# esp8285-miniboard-v1_0.net
KiCad netlist of a schematic drawn in EAGLE
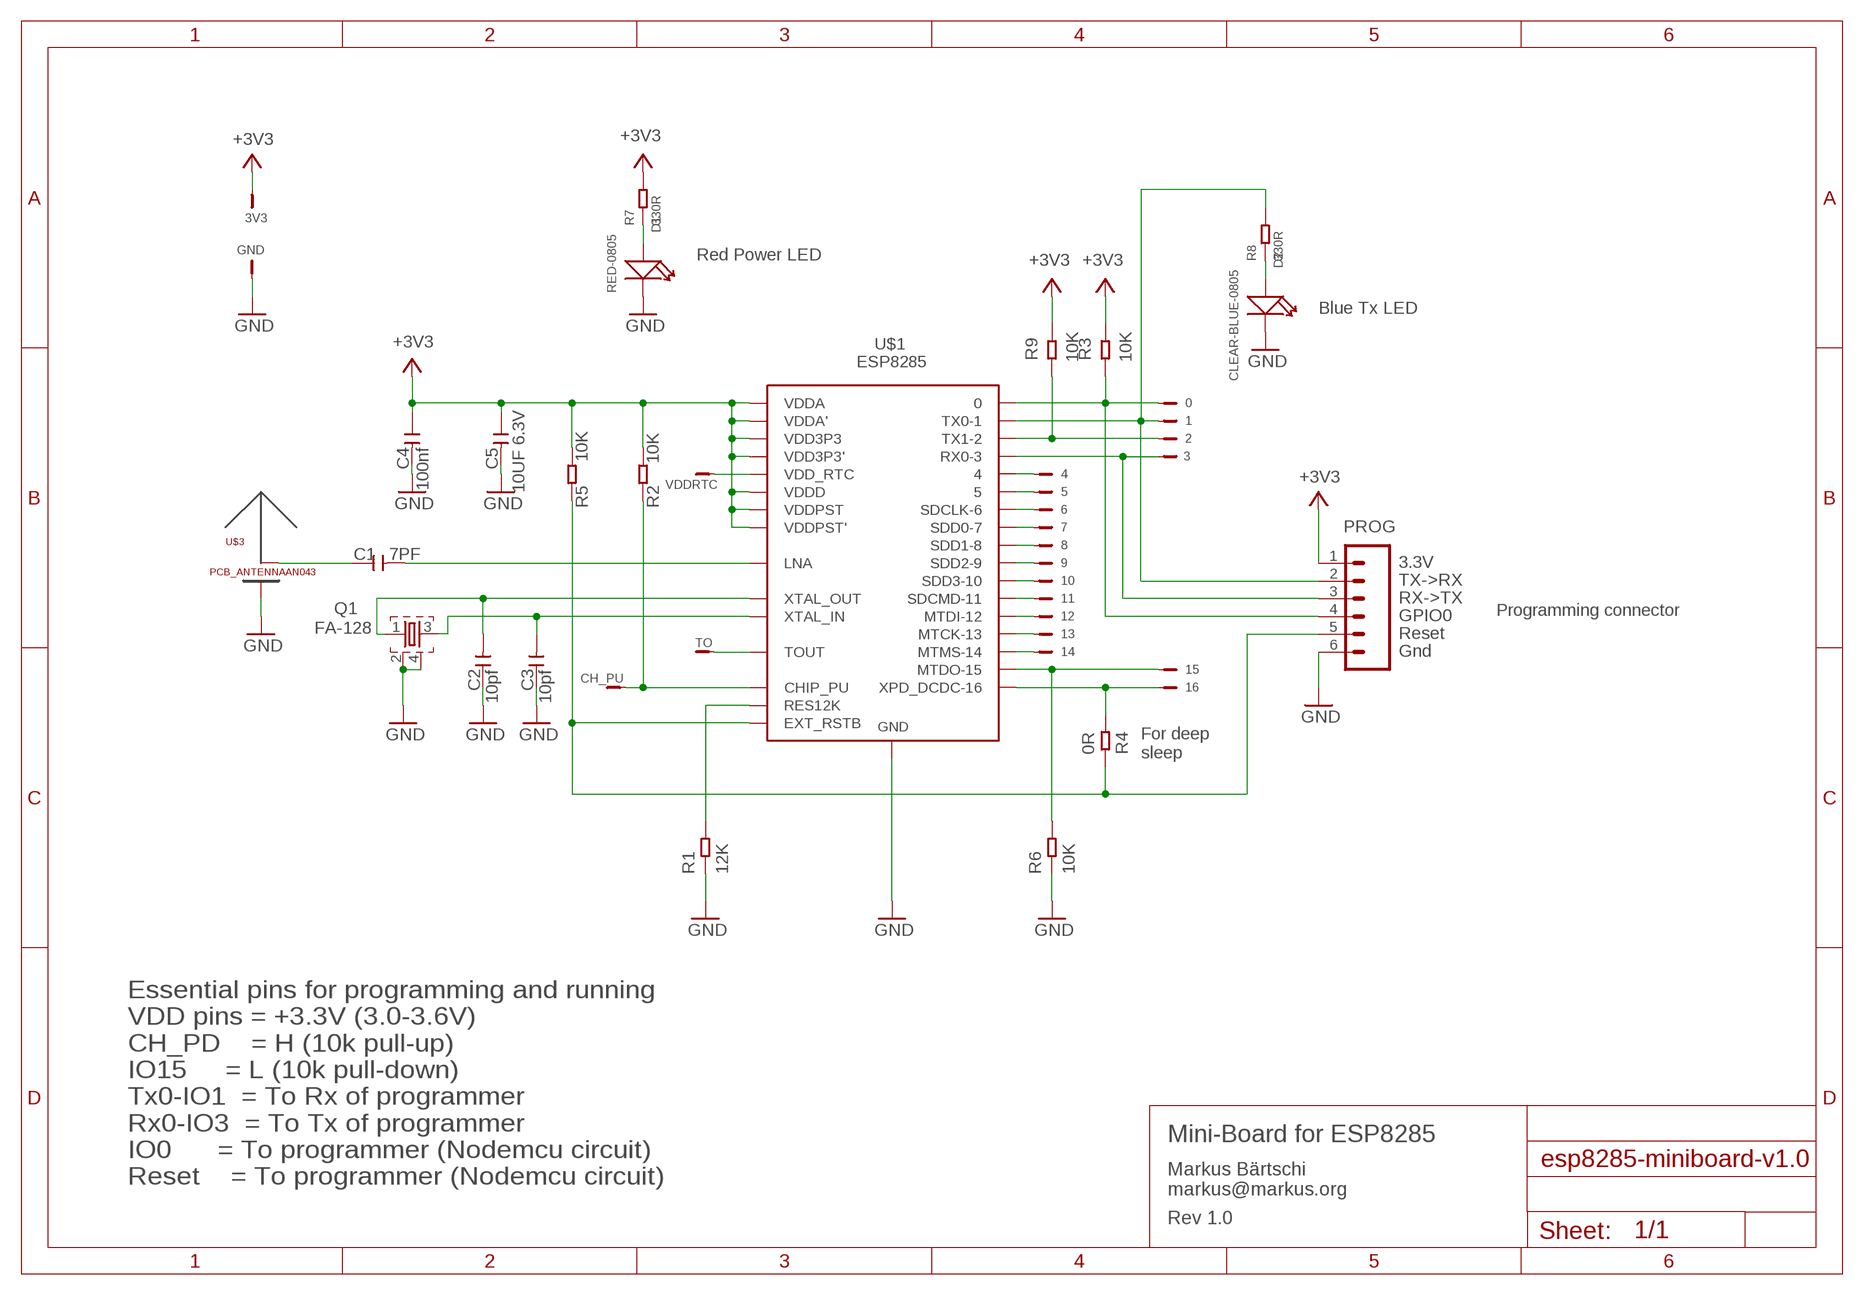
[diagram p0: schematic, sheet 1]

(export (version "E")
  (design (tool "Eeschema 10.0.6"))
  (components
    (comp (ref "0")
      (value "TESTPIN-1X1-SM")
      (footprint "eagle-import:TESTPIN-HDR1X01")
      (libsource (lib "eagle-import") (part "TESTPIN-1X1-SM"))
    )
    (comp (ref "1")
      (value "TESTPIN-1X1-SM")
      (footprint "eagle-import:TESTPIN-HDR1X01")
      (libsource (lib "eagle-import") (part "TESTPIN-1X1-SM"))
    )
    (comp (ref "2")
      (value "TESTPIN-1X1-SM")
      (footprint "eagle-import:TESTPIN-HDR1X01")
      (libsource (lib "eagle-import") (part "TESTPIN-1X1-SM"))
    )
    (comp (ref "3")
      (value "TESTPIN-1X1-SM")
      (footprint "eagle-import:TESTPIN-HDR1X01")
      (libsource (lib "eagle-import") (part "TESTPIN-1X1-SM"))
    )
    (comp (ref "3V3")
      (value "TESTPIN-1X1-SM")
      (footprint "eagle-import:TESTPIN-HDR1X01")
      (libsource (lib "eagle-import") (part "TESTPIN-1X1-SM"))
    )
    (comp (ref "4")
      (value "TESTPIN-1X1-SM")
      (footprint "eagle-import:TESTPIN-HDR1X01")
      (libsource (lib "eagle-import") (part "TESTPIN-1X1-SM"))
    )
    (comp (ref "5")
      (value "TESTPIN-1X1-SM")
      (footprint "eagle-import:TESTPIN-HDR1X01")
      (libsource (lib "eagle-import") (part "TESTPIN-1X1-SM"))
    )
    (comp (ref "6")
      (value "TESTPIN-1X1-SM")
      (footprint "eagle-import:TESTPIN-HDR1X01")
      (libsource (lib "eagle-import") (part "TESTPIN-1X1-SM"))
    )
    (comp (ref "7")
      (value "TESTPIN-1X1-SM")
      (footprint "eagle-import:TESTPIN-HDR1X01")
      (libsource (lib "eagle-import") (part "TESTPIN-1X1-SM"))
    )
    (comp (ref "8")
      (value "TESTPIN-1X1-SM")
      (footprint "eagle-import:TESTPIN-HDR1X01")
      (libsource (lib "eagle-import") (part "TESTPIN-1X1-SM"))
    )
    (comp (ref "9")
      (value "TESTPIN-1X1-SM")
      (footprint "eagle-import:TESTPIN-HDR1X01")
      (libsource (lib "eagle-import") (part "TESTPIN-1X1-SM"))
    )
    (comp (ref "10")
      (value "TESTPIN-1X1-SM")
      (footprint "eagle-import:TESTPIN-HDR1X01")
      (libsource (lib "eagle-import") (part "TESTPIN-1X1-SM"))
    )
    (comp (ref "11")
      (value "TESTPIN-1X1-SM")
      (footprint "eagle-import:TESTPIN-HDR1X01")
      (libsource (lib "eagle-import") (part "TESTPIN-1X1-SM"))
    )
    (comp (ref "12")
      (value "TESTPIN-1X1-SM")
      (footprint "eagle-import:TESTPIN-HDR1X01")
      (libsource (lib "eagle-import") (part "TESTPIN-1X1-SM"))
    )
    (comp (ref "13")
      (value "TESTPIN-1X1-SM")
      (footprint "eagle-import:TESTPIN-HDR1X01")
      (libsource (lib "eagle-import") (part "TESTPIN-1X1-SM"))
    )
    (comp (ref "14")
      (value "TESTPIN-1X1-SM")
      (footprint "eagle-import:TESTPIN-HDR1X01")
      (libsource (lib "eagle-import") (part "TESTPIN-1X1-SM"))
    )
    (comp (ref "15")
      (value "TESTPIN-1X1-SM")
      (footprint "eagle-import:TESTPIN-HDR1X01")
      (libsource (lib "eagle-import") (part "TESTPIN-1X1-SM"))
    )
    (comp (ref "16")
      (value "TESTPIN-1X1-SM")
      (footprint "eagle-import:TESTPIN-HDR1X01")
      (libsource (lib "eagle-import") (part "TESTPIN-1X1-SM"))
    )
    (comp (ref "C1")
      (value "7PF")
      (footprint "eagle-import:C0603")
      (libsource (lib "eagle-import") (part "CERAMIC-7PF-50V-0.5PF-NPO(0603)"))
    )
    (comp (ref "C2")
      (value "10pf")
      (footprint "eagle-import:C0603")
      (libsource (lib "eagle-import") (part "CERAMIC-10PF-50V-5%-NPO(0603)"))
    )
    (comp (ref "C3")
      (value "10pf")
      (footprint "eagle-import:C0603")
      (libsource (lib "eagle-import") (part "CERAMIC-10PF-50V-5%-NPO(0603)"))
    )
    (comp (ref "C4")
      (value "100nf")
      (footprint "eagle-import:C0603")
      (fields (field (name "MPN") "CC0603KRX7R9BB104"))
      (libsource (lib "eagle-import") (part "CERAMIC-100NF-50V-10%-X7R(0603)"))
    )
    (comp (ref "C5")
      (value "10UF 6.3V")
      (footprint "eagle-import:C0603")
      (fields (field (name "MPN") "CC0603MRX5R5BB106"))
      (libsource (lib "eagle-import") (part "CERAMIC-10UF-6.3V-20%-X5R(0603)"))
    )
    (comp (ref "CH_PU")
      (value "TESTPIN-1X1-SM")
      (footprint "eagle-import:TESTPIN-HDR1X01")
      (libsource (lib "eagle-import") (part "TESTPIN-1X1-SM"))
    )
    (comp (ref "D1")
      (value "RED-0805")
      (footprint "eagle-import:LED-0805")
      (fields (field (name "MPN") "17-215SURC/S530-A2/TR8"))
      (libsource (lib "eagle-import") (part "SMD-LED-CLEAR-RED(0805)"))
    )
    (comp (ref "D2")
      (value "CLEAR-BLUE-0805")
      (footprint "eagle-import:LED-0805")
      (fields (field (name "MPN") "EL-17-215/BHC-AN1P2/3T"))
      (libsource (lib "eagle-import") (part "SMD-LED-CLEAR-BLUE(0805)"))
    )
    (comp (ref "GND")
      (value "TESTPIN-1X1-SM")
      (footprint "eagle-import:TESTPIN-HDR1X01")
      (libsource (lib "eagle-import") (part "TESTPIN-1X1-SM"))
    )
    (comp (ref "PROG")
      (value "M06SIP")
      (footprint "eagle-import:1X06")
      (libsource (lib "eagle-import") (part "M06SIP"))
    )
    (comp (ref "Q1")
      (value "FA-128")
      (footprint "eagle-import:FA-128")
      (libsource (lib "eagle-import") (part "FA-128"))
    )
    (comp (ref "R1")
      (value "12K")
      (footprint "eagle-import:R0603")
      (fields (field (name "MPN") "RC0603FR-0712KL"))
      (libsource (lib "eagle-import") (part "SMD-RES-12K-1%-1/10W(0603)"))
    )
    (comp (ref "R2")
      (value "10K")
      (footprint "eagle-import:R0603")
      (fields (field (name "MPN") "RC0603FR-0710KL"))
      (libsource (lib "eagle-import") (part "SMD-RES-10K-1%-1/10W(0603)"))
    )
    (comp (ref "R3")
      (value "10K")
      (footprint "eagle-import:R0603")
      (fields (field (name "MPN") "RC0603FR-0710KL"))
      (libsource (lib "eagle-import") (part "SMD-RES-10K-1%-1/10W(0603)"))
    )
    (comp (ref "R4")
      (value "0R")
      (footprint "eagle-import:R0603")
      (fields (field (name "MPN") "RC0603JR-070RL"))
      (libsource (lib "eagle-import") (part "SMD-RES-0R-5%-1/10W(0603)"))
    )
    (comp (ref "R5")
      (value "10K")
      (footprint "eagle-import:R0603")
      (fields (field (name "MPN") "RC0603FR-0710KL"))
      (libsource (lib "eagle-import") (part "SMD-RES-10K-1%-1/10W(0603)"))
    )
    (comp (ref "R6")
      (value "10K")
      (footprint "eagle-import:R0603")
      (fields (field (name "MPN") "RC0603FR-0710KL"))
      (libsource (lib "eagle-import") (part "SMD-RES-10K-1%-1/10W(0603)"))
    )
    (comp (ref "R7")
      (value "330R")
      (footprint "eagle-import:R0603")
      (fields (field (name "MPN") "RC0603FR-07330RL"))
      (libsource (lib "eagle-import") (part "SMD-RES-330R-1%-1/10W(0603)"))
    )
    (comp (ref "R8")
      (value "330R")
      (footprint "eagle-import:R0603")
      (fields (field (name "MPN") "RC0603FR-07330RL"))
      (libsource (lib "eagle-import") (part "SMD-RES-330R-1%-1/10W(0603)"))
    )
    (comp (ref "R9")
      (value "10K")
      (footprint "eagle-import:R0603")
      (fields (field (name "MPN") "RC0603FR-0710KL"))
      (libsource (lib "eagle-import") (part "SMD-RES-10K-1%-1/10W(0603)"))
    )
    (comp (ref "TO")
      (value "TESTPIN-1X1-SM")
      (footprint "eagle-import:TESTPIN-HDR1X01")
      (libsource (lib "eagle-import") (part "TESTPIN-1X1-SM"))
    )
    (comp (ref "U$1")
      (value "ESP8285")
      (footprint "eagle-import:QFN-32")
      (libsource (lib "eagle-import") (part "ESP8285"))
    )
    (comp (ref "U$3")
      (value "PCB_ANTENNAAN043")
      (footprint "eagle-import:PCB_ANTENNA_TI-AN043")
      (libsource (lib "eagle-import") (part "PCB_ANTENNAAN043"))
    )
    (comp (ref "VDDRTC")
      (value "TESTPIN-1X1-SM")
      (footprint "eagle-import:TESTPIN-HDR1X01")
      (libsource (lib "eagle-import") (part "TESTPIN-1X1-SM"))
    )
  )
  (nets
    (net (code "1") (name "+3V3") (class "Default")
      (node (ref "3V3") (pin "1") (pinfunction "1_1") (pintype "passive"))
      (node (ref "C4") (pin "1") (pinfunction "1_1") (pintype "passive"))
      (node (ref "C5") (pin "1") (pinfunction "1_1") (pintype "passive"))
      (node (ref "PROG") (pin "1") (pinfunction "1_1") (pintype "passive"))
      (node (ref "R2") (pin "2") (pinfunction "2_2") (pintype "passive"))
      (node (ref "R3") (pin "2") (pinfunction "2_2") (pintype "passive"))
      (node (ref "R5") (pin "2") (pinfunction "2_2") (pintype "passive"))
      (node (ref "R7") (pin "2") (pinfunction "2_2") (pintype "passive"))
      (node (ref "R9") (pin "2") (pinfunction "2_2") (pintype "passive"))
      (node (ref "U$1") (pin "P$1") (pinfunction "VDDA_P$1") (pintype "power_in"))
      (node (ref "U$1") (pin "P$11") (pinfunction "VDDPST_P$11") (pintype "power_in"))
      (node (ref "U$1") (pin "P$17") (pinfunction "VDDPST'_P$17") (pintype "power_in"))
      (node (ref "U$1") (pin "P$29") (pinfunction "VDDD_P$29") (pintype "power_in"))
      (node (ref "U$1") (pin "P$3") (pinfunction "VDD3P3_P$3") (pintype "power_in"))
      (node (ref "U$1") (pin "P$30") (pinfunction "VDDA'_P$30") (pintype "power_in"))
      (node (ref "U$1") (pin "P$4") (pinfunction "VDD3P3'_P$4") (pintype "power_in"))
    )
    (net (code "2") (name "GND") (class "Default")
      (node (ref "C2") (pin "1") (pinfunction "1_1") (pintype "passive"))
      (node (ref "C3") (pin "1") (pinfunction "1_1") (pintype "passive"))
      (node (ref "C4") (pin "2") (pinfunction "2_2") (pintype "passive"))
      (node (ref "C5") (pin "2") (pinfunction "2_2") (pintype "passive"))
      (node (ref "D1") (pin "-") (pinfunction "-_-") (pintype "passive"))
      (node (ref "D2") (pin "-") (pinfunction "-_-") (pintype "passive"))
      (node (ref "GND") (pin "1") (pinfunction "1_1") (pintype "passive"))
      (node (ref "PROG") (pin "6") (pinfunction "6_6") (pintype "passive"))
      (node (ref "Q1") (pin "2") (pinfunction "2_2") (pintype "passive"))
      (node (ref "Q1") (pin "4") (pinfunction "4_4") (pintype "passive"))
      (node (ref "R1") (pin "1") (pinfunction "1_1") (pintype "passive"))
      (node (ref "R6") (pin "1") (pinfunction "1_1") (pintype "passive"))
      (node (ref "U$1") (pin "33-GND") (pinfunction "GND_33-GND") (pintype "power_in"))
      (node (ref "U$3") (pin "GND") (pinfunction "GND_GND") (pintype "power_in"))
    )
    (net (code "3") (name "Net-(D1-Pad+)") (class "Default")
      (node (ref "D1") (pin "+") (pinfunction "+_+") (pintype "passive"))
      (node (ref "R7") (pin "1") (pinfunction "1_1") (pintype "passive"))
    )
    (net (code "4") (name "Net-(D2-Pad+)") (class "Default")
      (node (ref "D2") (pin "+") (pinfunction "+_+") (pintype "passive"))
      (node (ref "R8") (pin "1") (pinfunction "1_1") (pintype "passive"))
    )
    (net (code "5") (name "Net-(U$1-0)") (class "Default")
      (node (ref "0") (pin "1") (pinfunction "1_1") (pintype "passive"))
      (node (ref "PROG") (pin "4") (pinfunction "4_4") (pintype "passive"))
      (node (ref "R3") (pin "1") (pinfunction "1_1") (pintype "passive"))
      (node (ref "U$1") (pin "P$15") (pinfunction "0_P$15") (pintype "bidirectional"))
    )
    (net (code "6") (name "Net-(U$1-4)") (class "Default")
      (node (ref "4") (pin "1") (pinfunction "1_1") (pintype "passive"))
      (node (ref "U$1") (pin "P$16") (pinfunction "4_P$16") (pintype "bidirectional"))
    )
    (net (code "7") (name "Net-(U$1-5)") (class "Default")
      (node (ref "5") (pin "1") (pinfunction "1_1") (pintype "passive"))
      (node (ref "U$1") (pin "P$24") (pinfunction "5_P$24") (pintype "bidirectional"))
    )
    (net (code "8") (name "Net-(U$1-CHIP_PU)") (class "Default")
      (node (ref "CH_PU") (pin "1") (pinfunction "1_1") (pintype "passive"))
      (node (ref "R2") (pin "1") (pinfunction "1_1") (pintype "passive"))
      (node (ref "U$1") (pin "P$7") (pinfunction "CHIP_PU_P$7") (pintype "input"))
    )
    (net (code "9") (name "Net-(U$1-EXT_RSTB)") (class "Default")
      (node (ref "PROG") (pin "5") (pinfunction "5_5") (pintype "passive"))
      (node (ref "R4") (pin "2") (pinfunction "2_2") (pintype "passive"))
      (node (ref "R5") (pin "1") (pinfunction "1_1") (pintype "passive"))
      (node (ref "U$1") (pin "P$32") (pinfunction "EXT_RSTB_P$32") (pintype "input"))
    )
    (net (code "10") (name "Net-(U$1-LNA)") (class "Default")
      (node (ref "C1") (pin "2") (pinfunction "2_2") (pintype "passive"))
      (node (ref "U$1") (pin "P$2") (pinfunction "LNA_P$2") (pintype "bidirectional"))
    )
    (net (code "11") (name "Net-(U$1-MTCK-13)") (class "Default")
      (node (ref "13") (pin "1") (pinfunction "1_1") (pintype "passive"))
      (node (ref "U$1") (pin "P$12") (pinfunction "MTCK-13_P$12") (pintype "bidirectional"))
    )
    (net (code "12") (name "Net-(U$1-MTDI-12)") (class "Default")
      (node (ref "12") (pin "1") (pinfunction "1_1") (pintype "passive"))
      (node (ref "U$1") (pin "P$10") (pinfunction "MTDI-12_P$10") (pintype "bidirectional"))
    )
    (net (code "13") (name "Net-(U$1-MTDO-15)") (class "Default")
      (node (ref "15") (pin "1") (pinfunction "1_1") (pintype "passive"))
      (node (ref "R6") (pin "2") (pinfunction "2_2") (pintype "passive"))
      (node (ref "U$1") (pin "P$13") (pinfunction "MTDO-15_P$13") (pintype "bidirectional"))
    )
    (net (code "14") (name "Net-(U$1-MTMS-14)") (class "Default")
      (node (ref "14") (pin "1") (pinfunction "1_1") (pintype "passive"))
      (node (ref "U$1") (pin "P$9") (pinfunction "MTMS-14_P$9") (pintype "bidirectional"))
    )
    (net (code "15") (name "Net-(U$1-RES12K)") (class "Default")
      (node (ref "R1") (pin "2") (pinfunction "2_2") (pintype "passive"))
      (node (ref "U$1") (pin "P$31") (pinfunction "RES12K_P$31") (pintype "input"))
    )
    (net (code "16") (name "Net-(U$1-RX0-3)") (class "Default")
      (node (ref "3") (pin "1") (pinfunction "1_1") (pintype "passive"))
      (node (ref "PROG") (pin "3") (pinfunction "3_3") (pintype "passive"))
      (node (ref "U$1") (pin "P$25") (pinfunction "RX0-3_P$25") (pintype "bidirectional"))
    )
    (net (code "17") (name "Net-(U$1-SDCLK-6)") (class "Default")
      (node (ref "6") (pin "1") (pinfunction "1_1") (pintype "passive"))
      (node (ref "U$1") (pin "P$21") (pinfunction "SDCLK-6_P$21") (pintype "bidirectional"))
    )
    (net (code "18") (name "Net-(U$1-SDCMD-11)") (class "Default")
      (node (ref "11") (pin "1") (pinfunction "1_1") (pintype "passive"))
      (node (ref "U$1") (pin "P$20") (pinfunction "SDCMD-11_P$20") (pintype "bidirectional"))
    )
    (net (code "19") (name "Net-(U$1-SDD0-7)") (class "Default")
      (node (ref "7") (pin "1") (pinfunction "1_1") (pintype "passive"))
      (node (ref "U$1") (pin "P$22") (pinfunction "SDD0-7_P$22") (pintype "bidirectional"))
    )
    (net (code "20") (name "Net-(U$1-SDD1-8)") (class "Default")
      (node (ref "8") (pin "1") (pinfunction "1_1") (pintype "passive"))
      (node (ref "U$1") (pin "P$23") (pinfunction "SDD1-8_P$23") (pintype "bidirectional"))
    )
    (net (code "21") (name "Net-(U$1-SDD2-9)") (class "Default")
      (node (ref "9") (pin "1") (pinfunction "1_1") (pintype "passive"))
      (node (ref "U$1") (pin "P$18") (pinfunction "SDD2-9_P$18") (pintype "bidirectional"))
    )
    (net (code "22") (name "Net-(U$1-SDD3-10)") (class "Default")
      (node (ref "10") (pin "1") (pinfunction "1_1") (pintype "passive"))
      (node (ref "U$1") (pin "P$19") (pinfunction "SDD3-10_P$19") (pintype "bidirectional"))
    )
    (net (code "23") (name "Net-(U$1-TOUT)") (class "Default")
      (node (ref "TO") (pin "1") (pinfunction "1_1") (pintype "passive"))
      (node (ref "U$1") (pin "P$6") (pinfunction "TOUT_P$6") (pintype "input"))
    )
    (net (code "24") (name "Net-(U$1-TX0-1)") (class "Default")
      (node (ref "1") (pin "1") (pinfunction "1_1") (pintype "passive"))
      (node (ref "PROG") (pin "2") (pinfunction "2_2") (pintype "passive"))
      (node (ref "R8") (pin "2") (pinfunction "2_2") (pintype "passive"))
      (node (ref "U$1") (pin "P$26") (pinfunction "TX0-1_P$26") (pintype "bidirectional"))
    )
    (net (code "25") (name "Net-(U$1-TX1-2)") (class "Default")
      (node (ref "2") (pin "1") (pinfunction "1_1") (pintype "passive"))
      (node (ref "R9") (pin "1") (pinfunction "1_1") (pintype "passive"))
      (node (ref "U$1") (pin "P$14") (pinfunction "TX1-2_P$14") (pintype "bidirectional"))
    )
    (net (code "26") (name "Net-(U$1-VDD_RTC)") (class "Default")
      (node (ref "U$1") (pin "P$5") (pinfunction "VDD_RTC_P$5") (pintype "power_in"))
      (node (ref "VDDRTC") (pin "1") (pinfunction "1_1") (pintype "passive"))
    )
    (net (code "27") (name "Net-(U$1-XPD_DCDC-16)") (class "Default")
      (node (ref "16") (pin "1") (pinfunction "1_1") (pintype "passive"))
      (node (ref "R4") (pin "1") (pinfunction "1_1") (pintype "passive"))
      (node (ref "U$1") (pin "P$8") (pinfunction "XPD_DCDC-16_P$8") (pintype "bidirectional"))
    )
    (net (code "28") (name "Net-(U$1-XTAL_IN)") (class "Default")
      (node (ref "C3") (pin "2") (pinfunction "2_2") (pintype "passive"))
      (node (ref "Q1") (pin "3") (pinfunction "3_3") (pintype "passive"))
      (node (ref "U$1") (pin "P$28") (pinfunction "XTAL_IN_P$28") (pintype "input"))
    )
    (net (code "29") (name "Net-(U$1-XTAL_OUT)") (class "Default")
      (node (ref "C2") (pin "2") (pinfunction "2_2") (pintype "passive"))
      (node (ref "Q1") (pin "1") (pinfunction "1_1") (pintype "passive"))
      (node (ref "U$1") (pin "P$27") (pinfunction "XTAL_OUT_P$27") (pintype "output"))
    )
    (net (code "30") (name "Net-(U$3-AND)") (class "Default")
      (node (ref "C1") (pin "1") (pinfunction "1_1") (pintype "passive"))
      (node (ref "U$3") (pin "ANT") (pinfunction "AND_ANT") (pintype "bidirectional"))
    )
  )
)
